# design.net
KiCad netlist of a schematic drawn in Altium Designer
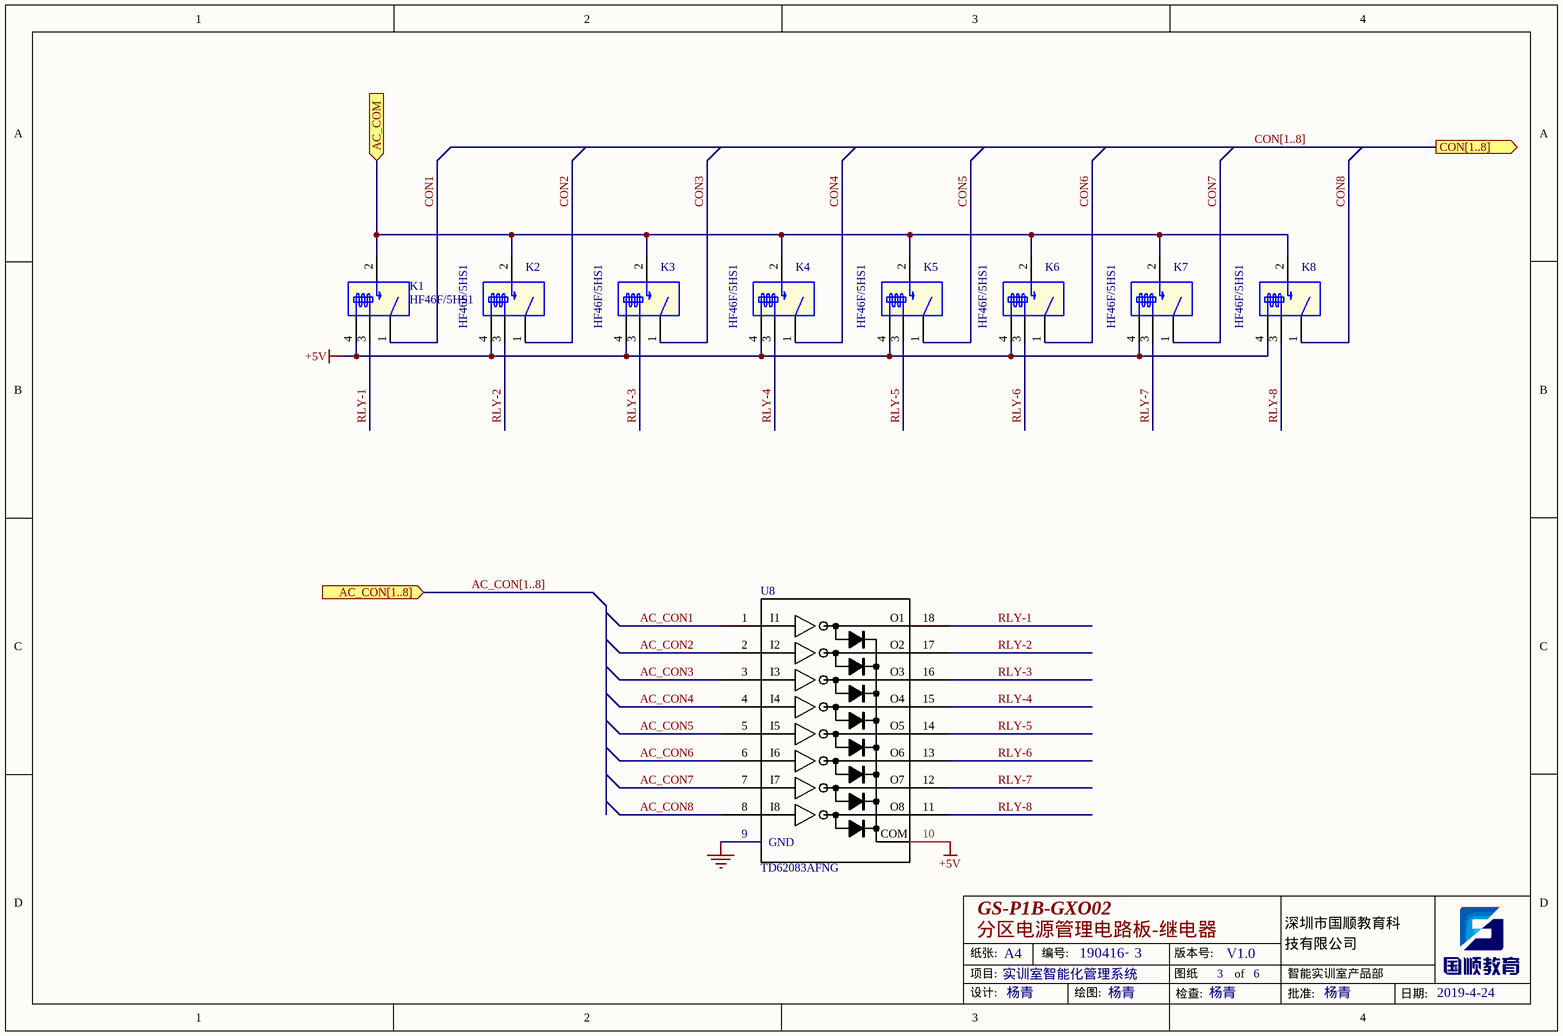
[diagram p0: 继电器输出.SchDoc]

(export (version "E")
  (design (tool "Eeschema 10.0.6"))
  (components
    (comp (ref "K1")
      (value "HF46F/5HS1")
      (footprint "RELAY_HF46F")
      (description "HF46F/5HS1,5V,容量 3A 250VAC/5A 30VDC,线圈功率200mW")
      (libsource (lib "继电器") (part "HF46F/5HS1-5VDC"))
    )
    (comp (ref "K2")
      (value "HF46F/5HS1")
      (footprint "RELAY_HF46F")
      (description "HF46F/5HS1,5V,容量 3A 250VAC/5A 30VDC,线圈功率200mW")
      (libsource (lib "继电器") (part "HF46F/5HS1-5VDC"))
    )
    (comp (ref "K3")
      (value "HF46F/5HS1")
      (footprint "RELAY_HF46F")
      (description "HF46F/5HS1,5V,容量 3A 250VAC/5A 30VDC,线圈功率200mW")
      (libsource (lib "继电器") (part "HF46F/5HS1-5VDC"))
    )
    (comp (ref "K4")
      (value "HF46F/5HS1")
      (footprint "RELAY_HF46F")
      (description "HF46F/5HS1,5V,容量 3A 250VAC/5A 30VDC,线圈功率200mW")
      (libsource (lib "继电器") (part "HF46F/5HS1-5VDC"))
    )
    (comp (ref "K5")
      (value "HF46F/5HS1")
      (footprint "RELAY_HF46F")
      (description "HF46F/5HS1,5V,容量 3A 250VAC/5A 30VDC,线圈功率200mW")
      (libsource (lib "继电器") (part "HF46F/5HS1-5VDC"))
    )
    (comp (ref "K6")
      (value "HF46F/5HS1")
      (footprint "RELAY_HF46F")
      (description "HF46F/5HS1,5V,容量 3A 250VAC/5A 30VDC,线圈功率200mW")
      (libsource (lib "继电器") (part "HF46F/5HS1-5VDC"))
    )
    (comp (ref "K7")
      (value "HF46F/5HS1")
      (footprint "RELAY_HF46F")
      (description "HF46F/5HS1,5V,容量 3A 250VAC/5A 30VDC,线圈功率200mW")
      (libsource (lib "继电器") (part "HF46F/5HS1-5VDC"))
    )
    (comp (ref "K8")
      (value "HF46F/5HS1")
      (footprint "RELAY_HF46F")
      (description "HF46F/5HS1,5V,容量 3A 250VAC/5A 30VDC,线圈功率200mW")
      (libsource (lib "继电器") (part "HF46F/5HS1-5VDC"))
    )
    (comp (ref "U8")
      (value "TD62083AFNG")
      (footprint "TSSOP18-0.65/4.4")
      (description "驱动IC")
      (libsource (lib "IC") (part "TD62083AFNG_TSSOP18_(LOGIC)"))
    )
  )
  (nets
    (net (code "1") (name "+5V") (class "Default")
      (node (ref "K1") (pin "4") (pinfunction "COIL2_4") (pintype "passive"))
      (node (ref "K2") (pin "4") (pinfunction "COIL2_4") (pintype "passive"))
      (node (ref "K3") (pin "4") (pinfunction "COIL2_4") (pintype "passive"))
      (node (ref "K4") (pin "4") (pinfunction "COIL2_4") (pintype "passive"))
      (node (ref "K5") (pin "4") (pinfunction "COIL2_4") (pintype "passive"))
      (node (ref "K6") (pin "4") (pinfunction "COIL2_4") (pintype "passive"))
      (node (ref "K7") (pin "4") (pinfunction "COIL2_4") (pintype "passive"))
      (node (ref "K8") (pin "4") (pinfunction "COIL2_4") (pintype "passive"))
      (node (ref "U8") (pin "10") (pinfunction "COM_10") (pintype "passive"))
    )
    (net (code "2") (name "/AC_COM") (class "Default")
      (node (ref "K1") (pin "2") (pinfunction "NO_2") (pintype "passive"))
      (node (ref "K2") (pin "2") (pinfunction "NO_2") (pintype "passive"))
      (node (ref "K3") (pin "2") (pinfunction "NO_2") (pintype "passive"))
      (node (ref "K4") (pin "2") (pinfunction "NO_2") (pintype "passive"))
      (node (ref "K5") (pin "2") (pinfunction "NO_2") (pintype "passive"))
      (node (ref "K6") (pin "2") (pinfunction "NO_2") (pintype "passive"))
      (node (ref "K7") (pin "2") (pinfunction "NO_2") (pintype "passive"))
      (node (ref "K8") (pin "2") (pinfunction "NO_2") (pintype "passive"))
    )
    (net (code "3") (name "/AC_CON1") (class "Default")
      (node (ref "U8") (pin "1") (pinfunction "I1_1") (pintype "passive"))
    )
    (net (code "4") (name "/AC_CON2") (class "Default")
      (node (ref "U8") (pin "2") (pinfunction "I2_2") (pintype "passive"))
    )
    (net (code "5") (name "/AC_CON3") (class "Default")
      (node (ref "U8") (pin "3") (pinfunction "I3_3") (pintype "passive"))
    )
    (net (code "6") (name "/AC_CON4") (class "Default")
      (node (ref "U8") (pin "4") (pinfunction "I4_4") (pintype "passive"))
    )
    (net (code "7") (name "/AC_CON5") (class "Default")
      (node (ref "U8") (pin "5") (pinfunction "I5_5") (pintype "passive"))
    )
    (net (code "8") (name "/AC_CON6") (class "Default")
      (node (ref "U8") (pin "6") (pinfunction "I6_6") (pintype "passive"))
    )
    (net (code "9") (name "/AC_CON7") (class "Default")
      (node (ref "U8") (pin "7") (pinfunction "I7_7") (pintype "passive"))
    )
    (net (code "10") (name "/AC_CON8") (class "Default")
      (node (ref "U8") (pin "8") (pinfunction "I8_8") (pintype "passive"))
    )
    (net (code "12") (name "/CON1") (class "Default")
      (node (ref "K1") (pin "1") (pinfunction "COM_1") (pintype "passive"))
    )
    (net (code "13") (name "/CON2") (class "Default")
      (node (ref "K2") (pin "1") (pinfunction "COM_1") (pintype "passive"))
    )
    (net (code "14") (name "/CON3") (class "Default")
      (node (ref "K3") (pin "1") (pinfunction "COM_1") (pintype "passive"))
    )
    (net (code "15") (name "/CON4") (class "Default")
      (node (ref "K4") (pin "1") (pinfunction "COM_1") (pintype "passive"))
    )
    (net (code "16") (name "/CON5") (class "Default")
      (node (ref "K5") (pin "1") (pinfunction "COM_1") (pintype "passive"))
    )
    (net (code "17") (name "/CON6") (class "Default")
      (node (ref "K6") (pin "1") (pinfunction "COM_1") (pintype "passive"))
    )
    (net (code "18") (name "/CON7") (class "Default")
      (node (ref "K7") (pin "1") (pinfunction "COM_1") (pintype "passive"))
    )
    (net (code "19") (name "/CON8") (class "Default")
      (node (ref "K8") (pin "1") (pinfunction "COM_1") (pintype "passive"))
    )
    (net (code "21") (name "/RLY-1") (class "Default")
      (node (ref "K1") (pin "3") (pinfunction "COIL1_3") (pintype "passive"))
      (node (ref "U8") (pin "18") (pinfunction "O1_18") (pintype "passive"))
    )
    (net (code "22") (name "/RLY-2") (class "Default")
      (node (ref "K2") (pin "3") (pinfunction "COIL1_3") (pintype "passive"))
      (node (ref "U8") (pin "17") (pinfunction "O2_17") (pintype "passive"))
    )
    (net (code "23") (name "/RLY-3") (class "Default")
      (node (ref "K3") (pin "3") (pinfunction "COIL1_3") (pintype "passive"))
      (node (ref "U8") (pin "16") (pinfunction "O3_16") (pintype "passive"))
    )
    (net (code "24") (name "/RLY-4") (class "Default")
      (node (ref "K4") (pin "3") (pinfunction "COIL1_3") (pintype "passive"))
      (node (ref "U8") (pin "15") (pinfunction "O4_15") (pintype "passive"))
    )
    (net (code "25") (name "/RLY-5") (class "Default")
      (node (ref "K5") (pin "3") (pinfunction "COIL1_3") (pintype "passive"))
      (node (ref "U8") (pin "14") (pinfunction "O5_14") (pintype "passive"))
    )
    (net (code "26") (name "/RLY-6") (class "Default")
      (node (ref "K6") (pin "3") (pinfunction "COIL1_3") (pintype "passive"))
      (node (ref "U8") (pin "13") (pinfunction "O6_13") (pintype "passive"))
    )
    (net (code "27") (name "/RLY-7") (class "Default")
      (node (ref "K7") (pin "3") (pinfunction "COIL1_3") (pintype "passive"))
      (node (ref "U8") (pin "12") (pinfunction "O7_12") (pintype "passive"))
    )
    (net (code "28") (name "/RLY-8") (class "Default")
      (node (ref "K8") (pin "3") (pinfunction "COIL1_3") (pintype "passive"))
      (node (ref "U8") (pin "11") (pinfunction "O8_11") (pintype "passive"))
    )
    (net (code "29") (name "GND") (class "Default")
      (node (ref "U8") (pin "9") (pinfunction "GND_9") (pintype "passive"))
    )
  )
)
